# Micro_Controller.net
KiCad netlist of a schematic drawn in Altium Designer
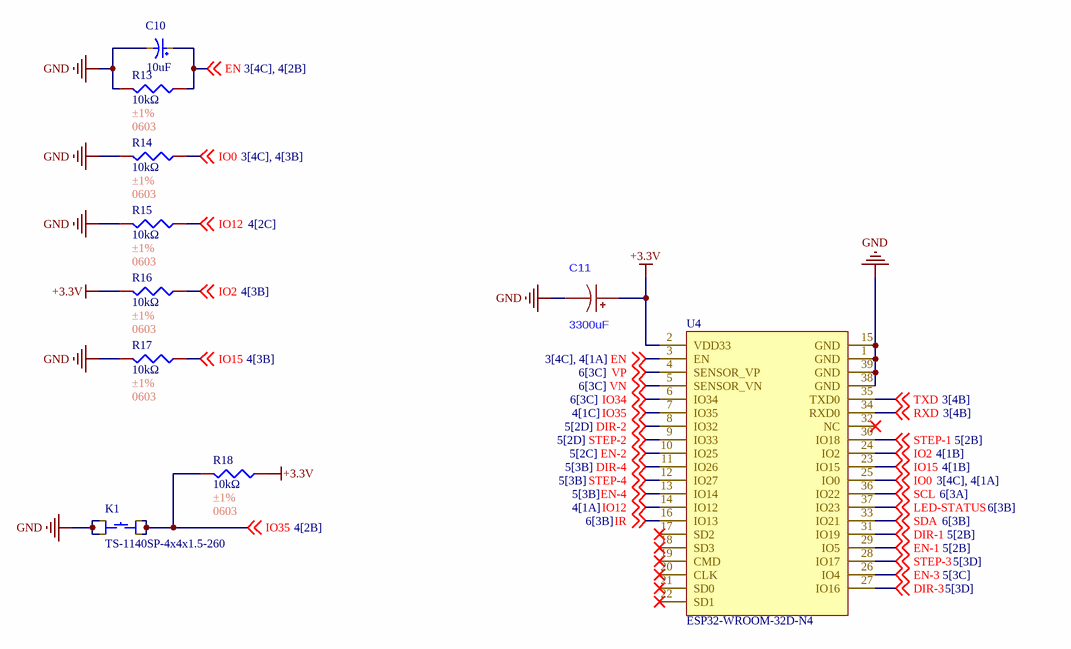
[diagram p0: Micro Controller.SchDoc]

(export (version "E")
  (design (tool "Eeschema 10.0.6"))
  (components
    (comp (ref "C10")
      (value "10uF")
      (footprint "C_TH_5x11mm")
      (description "10uF 50V ±20% Through Hole,D5xL11mm Aluminum Electrolytic Capacitors - Leaded ROHS")
      (fields (field (name "MANUFACTURER") "Rubycon") (field (name "MFR. PART #") "50YXF10MEFC5X11"))
      (libsource (lib "Capital") (part "C_10uF_5x11TH"))
    )
    (comp (ref "C11")
      (value "3300uF")
      (footprint "Through Hole,D8xL16mm")
      (description "3300uF ±20% 6.3V Through Hole,D8xL16mm 2000hrs")
      (fields (field (name "MANUFACTURER") "Honor Elec") (field (name "MFR. PART #") "HS0J338M0816PC"))
      (libsource (lib "Capital") (part "Through Hole,D8xL16mm"))
    )
    (comp (ref "K1")
      (value "TS-1140SP-4x4x1.5-260")
      (footprint "4x4x1.5")
      (description "SMD Tactile Switches ROHS")
      (fields (field (name "MANUFACTURER") "CAX") (field (name "LCSC PART #") "C49023394"))
      (libsource (lib "Switch") (part "TS-1140SP-4x4x1.5-260"))
    )
    (comp (ref "R13")
      (value "10kΩ")
      (footprint "R0603")
      (description "62.5mW Thick Film Resistor 50V ±1% ±200ppm/℃ 10Ω 0402 Chip Resistor - Surface Mount ROHS")
      (fields
        (field (name "MANUFACTURER") "YAGEO")
        (field (name "MFR. PART #") "RC0402FR-0710RL")
        (field (name "TOLERANCE") "±1%")
        (field (name "PACKAGE") "0603")
      )
      (libsource (lib "Resistor") (part "R0603_10kΩ_±1%"))
    )
    (comp (ref "R14")
      (value "10kΩ")
      (footprint "R0603")
      (description "62.5mW Thick Film Resistor 50V ±1% ±200ppm/℃ 10Ω 0402 Chip Resistor - Surface Mount ROHS")
      (fields
        (field (name "MANUFACTURER") "YAGEO")
        (field (name "MFR. PART #") "RC0402FR-0710RL")
        (field (name "TOLERANCE") "±1%")
        (field (name "PACKAGE") "0603")
      )
      (libsource (lib "Resistor") (part "R0603_10kΩ_±1%"))
    )
    (comp (ref "R15")
      (value "10kΩ")
      (footprint "R0603")
      (description "62.5mW Thick Film Resistor 50V ±1% ±200ppm/℃ 10Ω 0402 Chip Resistor - Surface Mount ROHS")
      (fields
        (field (name "MANUFACTURER") "YAGEO")
        (field (name "MFR. PART #") "RC0402FR-0710RL")
        (field (name "TOLERANCE") "±1%")
        (field (name "PACKAGE") "0603")
      )
      (libsource (lib "Resistor") (part "R0603_10kΩ_±1%"))
    )
    (comp (ref "R16")
      (value "10kΩ")
      (footprint "R0603")
      (description "62.5mW Thick Film Resistor 50V ±1% ±200ppm/℃ 10Ω 0402 Chip Resistor - Surface Mount ROHS")
      (fields
        (field (name "MANUFACTURER") "YAGEO")
        (field (name "MFR. PART #") "RC0402FR-0710RL")
        (field (name "TOLERANCE") "±1%")
        (field (name "PACKAGE") "0603")
      )
      (libsource (lib "Resistor") (part "R0603_10kΩ_±1%"))
    )
    (comp (ref "R17")
      (value "10kΩ")
      (footprint "R0603")
      (description "62.5mW Thick Film Resistor 50V ±1% ±200ppm/℃ 10Ω 0402 Chip Resistor - Surface Mount ROHS")
      (fields
        (field (name "MANUFACTURER") "YAGEO")
        (field (name "MFR. PART #") "RC0402FR-0710RL")
        (field (name "TOLERANCE") "±1%")
        (field (name "PACKAGE") "0603")
      )
      (libsource (lib "Resistor") (part "R0603_10kΩ_±1%"))
    )
    (comp (ref "R18")
      (value "10kΩ")
      (footprint "R0603")
      (description "62.5mW Thick Film Resistor 50V ±1% ±200ppm/℃ 10Ω 0402 Chip Resistor - Surface Mount ROHS")
      (fields
        (field (name "MANUFACTURER") "YAGEO")
        (field (name "MFR. PART #") "RC0402FR-0710RL")
        (field (name "TOLERANCE") "±1%")
        (field (name "PACKAGE") "0603")
      )
      (libsource (lib "Resistor") (part "R0603_10kΩ_±1%"))
    )
    (comp (ref "U4")
      (value "ESP32-WROOM-32D-N4")
      (footprint "ESP32-WROOM-32D-N4")
      (description "SMD,18x25.5mm WiFi Modules ROHS")
      (fields (field (name "MANUFACTURER") "ESPRESSIF") (field (name "LCSC PART #") "C473012"))
      (libsource (lib "MCU") (part "ESPRESSIF ESP32-WROOM-32D-N4"))
    )
  )
  (nets
    (net (code "1") (name "+3.3V") (class "Default")
      (node (ref "C11") (pin "1") (pinfunction "1_1") (pintype "passive"))
      (node (ref "R16") (pin "2") (pinfunction "2_2") (pintype "passive"))
      (node (ref "R18") (pin "1") (pinfunction "1_1") (pintype "passive"))
      (node (ref "U4") (pin "2") (pinfunction "VDD33_2") (pintype "passive"))
    )
    (net (code "2") (name "DIR-1") (class "Default")
      (node (ref "U4") (pin "31") (pinfunction "IO19_31") (pintype "passive"))
    )
    (net (code "3") (name "DIR-2") (class "Default")
      (node (ref "U4") (pin "8") (pinfunction "IO32_8") (pintype "passive"))
    )
    (net (code "4") (name "DIR-3") (class "Default")
      (node (ref "U4") (pin "27") (pinfunction "IO16_27") (pintype "passive"))
    )
    (net (code "5") (name "DIR-4") (class "Default")
      (node (ref "U4") (pin "11") (pinfunction "IO26_11") (pintype "passive"))
    )
    (net (code "6") (name "EN") (class "Default")
      (node (ref "C10") (pin "1") (pinfunction "1_1") (pintype "passive"))
      (node (ref "R13") (pin "1") (pinfunction "1_1") (pintype "passive"))
      (node (ref "U4") (pin "3") (pinfunction "EN_3") (pintype "passive"))
    )
    (net (code "7") (name "EN-1") (class "Default")
      (node (ref "U4") (pin "29") (pinfunction "IO5_29") (pintype "passive"))
    )
    (net (code "8") (name "EN-2") (class "Default")
      (node (ref "U4") (pin "10") (pinfunction "IO25_10") (pintype "passive"))
    )
    (net (code "9") (name "EN-3") (class "Default")
      (node (ref "U4") (pin "26") (pinfunction "IO4_26") (pintype "passive"))
    )
    (net (code "10") (name "EN-4") (class "Default")
      (node (ref "U4") (pin "13") (pinfunction "IO14_13") (pintype "passive"))
    )
    (net (code "11") (name "GND") (class "Default")
      (node (ref "C10") (pin "2") (pinfunction "2_2") (pintype "passive"))
      (node (ref "C11") (pin "2") (pinfunction "2_2") (pintype "passive"))
      (node (ref "K1") (pin "1") (pinfunction "1_1") (pintype "passive"))
      (node (ref "K1") (pin "3") (pinfunction "3_3") (pintype "passive"))
      (node (ref "R13") (pin "2") (pinfunction "2_2") (pintype "passive"))
      (node (ref "R14") (pin "2") (pinfunction "2_2") (pintype "passive"))
      (node (ref "R15") (pin "2") (pinfunction "2_2") (pintype "passive"))
      (node (ref "R17") (pin "2") (pinfunction "2_2") (pintype "passive"))
      (node (ref "U4") (pin "1") (pinfunction "GND_1") (pintype "passive"))
      (node (ref "U4") (pin "15") (pinfunction "GND_15") (pintype "passive"))
      (node (ref "U4") (pin "38") (pinfunction "GND_38") (pintype "passive"))
      (node (ref "U4") (pin "39") (pinfunction "GND_39") (pintype "passive"))
    )
    (net (code "12") (name "IO0") (class "Default")
      (node (ref "R14") (pin "1") (pinfunction "1_1") (pintype "passive"))
      (node (ref "U4") (pin "25") (pinfunction "IO0_25") (pintype "passive"))
    )
    (net (code "13") (name "IO2") (class "Default")
      (node (ref "R16") (pin "1") (pinfunction "1_1") (pintype "passive"))
      (node (ref "U4") (pin "24") (pinfunction "IO2_24") (pintype "passive"))
    )
    (net (code "14") (name "IO12") (class "Default")
      (node (ref "R15") (pin "1") (pinfunction "1_1") (pintype "passive"))
      (node (ref "U4") (pin "14") (pinfunction "IO12_14") (pintype "passive"))
    )
    (net (code "15") (name "IO15") (class "Default")
      (node (ref "R17") (pin "1") (pinfunction "1_1") (pintype "passive"))
      (node (ref "U4") (pin "23") (pinfunction "IO15_23") (pintype "passive"))
    )
    (net (code "16") (name "IO34") (class "Default")
      (node (ref "U4") (pin "6") (pinfunction "IO34_6") (pintype "passive"))
    )
    (net (code "17") (name "IO35") (class "Default")
      (node (ref "K1") (pin "2") (pinfunction "2_2") (pintype "passive"))
      (node (ref "K1") (pin "4") (pinfunction "4_4") (pintype "passive"))
      (node (ref "R18") (pin "2") (pinfunction "2_2") (pintype "passive"))
      (node (ref "U4") (pin "7") (pinfunction "IO35_7") (pintype "passive"))
    )
    (net (code "18") (name "IR") (class "Default")
      (node (ref "U4") (pin "16") (pinfunction "IO13_16") (pintype "passive"))
    )
    (net (code "19") (name "LED-STATUS") (class "Default")
      (node (ref "U4") (pin "37") (pinfunction "IO23_37") (pintype "passive"))
    )
    (net (code "20") (name "RXD") (class "Default")
      (node (ref "U4") (pin "34") (pinfunction "RXD0_34") (pintype "passive"))
    )
    (net (code "21") (name "SCL") (class "Default")
      (node (ref "U4") (pin "36") (pinfunction "IO22_36") (pintype "passive"))
    )
    (net (code "22") (name "SDA") (class "Default")
      (node (ref "U4") (pin "33") (pinfunction "IO21_33") (pintype "passive"))
    )
    (net (code "23") (name "STEP-1") (class "Default")
      (node (ref "U4") (pin "30") (pinfunction "IO18_30") (pintype "passive"))
    )
    (net (code "24") (name "STEP-2") (class "Default")
      (node (ref "U4") (pin "9") (pinfunction "IO33_9") (pintype "passive"))
    )
    (net (code "25") (name "STEP-3") (class "Default")
      (node (ref "U4") (pin "28") (pinfunction "IO17_28") (pintype "passive"))
    )
    (net (code "26") (name "STEP-4") (class "Default")
      (node (ref "U4") (pin "12") (pinfunction "IO27_12") (pintype "passive"))
    )
    (net (code "27") (name "TXD") (class "Default")
      (node (ref "U4") (pin "35") (pinfunction "TXD0_35") (pintype "passive"))
    )
    (net (code "28") (name "VN") (class "Default")
      (node (ref "U4") (pin "5") (pinfunction "SENSOR_VN_5") (pintype "passive"))
    )
    (net (code "29") (name "VP") (class "Default")
      (node (ref "U4") (pin "4") (pinfunction "SENSOR_VP_4") (pintype "passive"))
    )
    (net (code "30") (name "unconnected-(U4-CLK-Pad20)") (class "Default")
      (node (ref "U4") (pin "20") (pinfunction "CLK_20") (pintype "passive+no_connect"))
    )
    (net (code "31") (name "unconnected-(U4-CMD-Pad19)") (class "Default")
      (node (ref "U4") (pin "19") (pinfunction "CMD_19") (pintype "passive+no_connect"))
    )
    (net (code "32") (name "unconnected-(U4-NC-Pad32)") (class "Default")
      (node (ref "U4") (pin "32") (pinfunction "NC_32") (pintype "passive+no_connect"))
    )
    (net (code "33") (name "unconnected-(U4-SD0-Pad21)") (class "Default")
      (node (ref "U4") (pin "21") (pinfunction "SD0_21") (pintype "passive+no_connect"))
    )
    (net (code "34") (name "unconnected-(U4-SD1-Pad22)") (class "Default")
      (node (ref "U4") (pin "22") (pinfunction "SD1_22") (pintype "passive+no_connect"))
    )
    (net (code "35") (name "unconnected-(U4-SD2-Pad17)") (class "Default")
      (node (ref "U4") (pin "17") (pinfunction "SD2_17") (pintype "passive+no_connect"))
    )
    (net (code "36") (name "unconnected-(U4-SD3-Pad18)") (class "Default")
      (node (ref "U4") (pin "18") (pinfunction "SD3_18") (pintype "passive+no_connect"))
    )
  )
)
